# SN754410.net
KiCad netlist of a schematic drawn in EAGLE
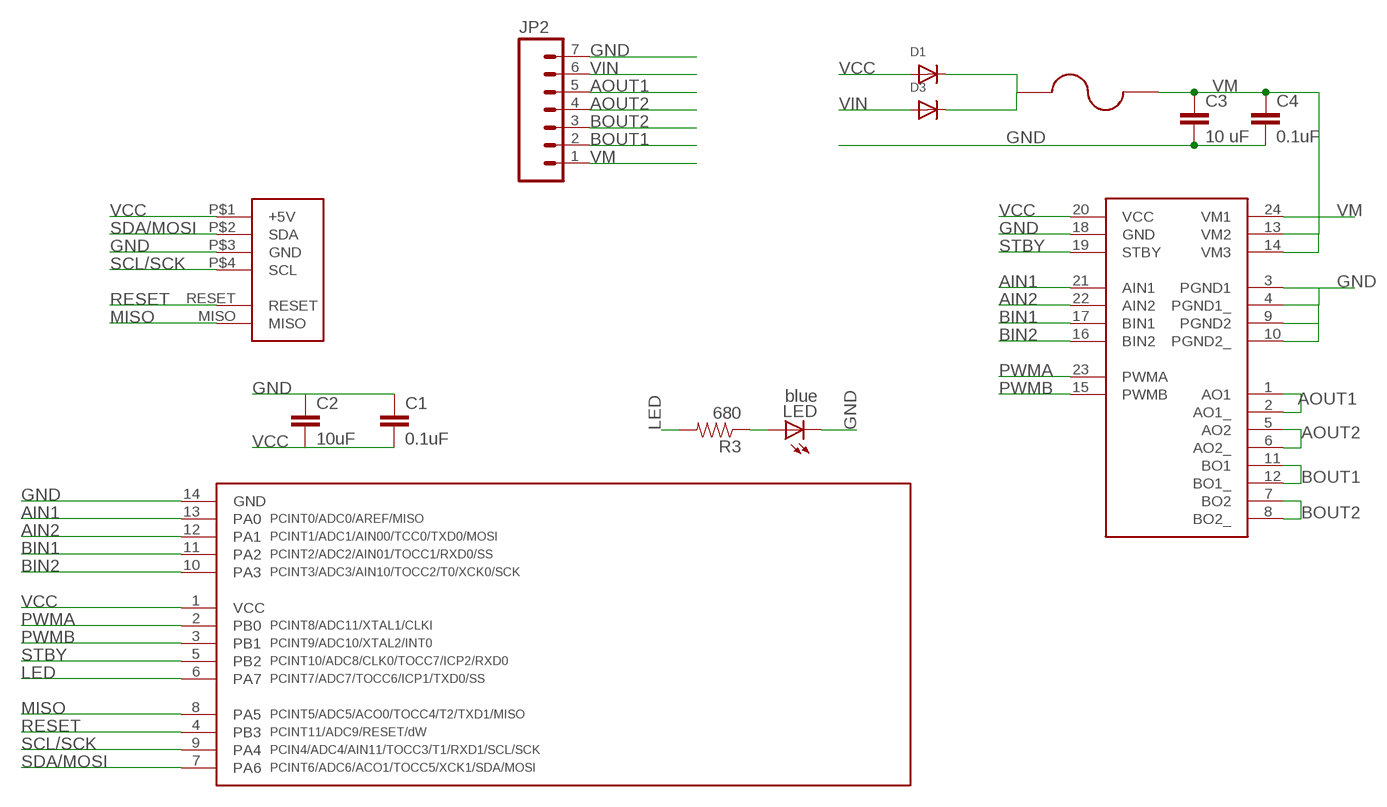
[diagram p0: schematic, sheet 1]

(export (version "E")
  (design (tool "Eeschema 10.0.6"))
  (components
    (comp (ref "C1")
      (value "0.1uF")
      (footprint "eagle-import:0805")
      (libsource (lib "eagle-import") (part "CAP0805"))
    )
    (comp (ref "C2")
      (value "10uF")
      (footprint "eagle-import:0805")
      (libsource (lib "eagle-import") (part "CAP0805"))
    )
    (comp (ref "C3")
      (value "10 uF")
      (footprint "eagle-import:0805")
      (libsource (lib "eagle-import") (part "CAP0805"))
    )
    (comp (ref "C4")
      (value "0.1uF")
      (footprint "eagle-import:0805")
      (libsource (lib "eagle-import") (part "CAP0805"))
    )
    (comp (ref "D1")
      (value "DIODESOD-123")
      (footprint "eagle-import:SOD-123")
      (libsource (lib "eagle-import") (part "DIODESOD-123"))
    )
    (comp (ref "D3")
      (value "DIODESOD-123")
      (footprint "eagle-import:SOD-123")
      (libsource (lib "eagle-import") (part "DIODESOD-123"))
    )
    (comp (ref "JP2")
      (value "M07")
      (footprint "eagle-import:1X07")
      (libsource (lib "eagle-import") (part "M07"))
    )
    (comp (ref "LED")
      (value "blue")
      (footprint "eagle-import:CHIPLED_1206")
      (libsource (lib "eagle-import") (part "LEDCHIPLED_1206"))
    )
    (comp (ref "R3")
      (value "680")
      (footprint "eagle-import:0805")
      (libsource (lib "eagle-import") (part "RESISTOR0805-RES"))
    )
    (comp (ref "U$1")
      (value "TB6612FNG")
      (footprint "eagle-import:SSOP-24")
      (libsource (lib "eagle-import") (part "TB6612FNG"))
    )
    (comp (ref "U$2")
      (value "FUSE")
      (footprint "eagle-import:1812")
      (libsource (lib "eagle-import") (part "FUSE"))
    )
    (comp (ref "U$3")
      (value "TINY841")
      (footprint "eagle-import:SOIC14")
      (libsource (lib "eagle-import") (part "TINY841"))
    )
    (comp (ref "U$4")
      (value "FOOTPRINT")
      (footprint "eagle-import:FOOTPRINT")
      (libsource (lib "eagle-import") (part "FOOTPRINT"))
    )
  )
  (nets
    (net (code "1") (name "/AIN1") (class "Default")
      (node (ref "U$1") (pin "21") (pinfunction "AIN1_21") (pintype "bidirectional"))
      (node (ref "U$3") (pin "13") (pinfunction "PA0_13") (pintype "bidirectional"))
    )
    (net (code "2") (name "/AIN2") (class "Default")
      (node (ref "U$1") (pin "22") (pinfunction "AIN2_22") (pintype "bidirectional"))
      (node (ref "U$3") (pin "12") (pinfunction "PA1_12") (pintype "bidirectional"))
    )
    (net (code "3") (name "/AOUT1") (class "Default")
      (node (ref "JP2") (pin "5") (pinfunction "5_5") (pintype "passive"))
      (node (ref "U$1") (pin "1") (pinfunction "AO1_1") (pintype "bidirectional"))
      (node (ref "U$1") (pin "2") (pinfunction "AO1__2") (pintype "bidirectional"))
    )
    (net (code "4") (name "/AOUT2") (class "Default")
      (node (ref "JP2") (pin "4") (pinfunction "4_4") (pintype "passive"))
      (node (ref "U$1") (pin "5") (pinfunction "AO2_5") (pintype "bidirectional"))
      (node (ref "U$1") (pin "6") (pinfunction "AO2__6") (pintype "bidirectional"))
    )
    (net (code "5") (name "/BIN1") (class "Default")
      (node (ref "U$1") (pin "17") (pinfunction "BIN1_17") (pintype "bidirectional"))
      (node (ref "U$3") (pin "11") (pinfunction "PA2_11") (pintype "bidirectional"))
    )
    (net (code "6") (name "/BIN2") (class "Default")
      (node (ref "U$1") (pin "16") (pinfunction "BIN2_16") (pintype "bidirectional"))
      (node (ref "U$3") (pin "10") (pinfunction "PA3_10") (pintype "bidirectional"))
    )
    (net (code "7") (name "/BOUT1") (class "Default")
      (node (ref "JP2") (pin "2") (pinfunction "2_2") (pintype "passive"))
      (node (ref "U$1") (pin "11") (pinfunction "BO1_11") (pintype "bidirectional"))
      (node (ref "U$1") (pin "12") (pinfunction "BO1__12") (pintype "bidirectional"))
    )
    (net (code "8") (name "/BOUT2") (class "Default")
      (node (ref "JP2") (pin "3") (pinfunction "3_3") (pintype "passive"))
      (node (ref "U$1") (pin "7") (pinfunction "BO2_7") (pintype "bidirectional"))
      (node (ref "U$1") (pin "8") (pinfunction "BO2__8") (pintype "bidirectional"))
    )
    (net (code "9") (name "/GND") (class "Default")
      (node (ref "C1") (pin "1") (pinfunction "1_1") (pintype "passive"))
      (node (ref "C2") (pin "1") (pinfunction "1_1") (pintype "passive"))
      (node (ref "C3") (pin "2") (pinfunction "2_2") (pintype "passive"))
      (node (ref "C4") (pin "2") (pinfunction "2_2") (pintype "passive"))
      (node (ref "JP2") (pin "7") (pinfunction "7_7") (pintype "passive"))
      (node (ref "LED") (pin "C") (pinfunction "C_C") (pintype "passive"))
      (node (ref "U$1") (pin "10") (pinfunction "PGND2__10") (pintype "bidirectional"))
      (node (ref "U$1") (pin "18") (pinfunction "GND_18") (pintype "bidirectional"))
      (node (ref "U$1") (pin "3") (pinfunction "PGND1_3") (pintype "bidirectional"))
      (node (ref "U$1") (pin "4") (pinfunction "PGND1__4") (pintype "bidirectional"))
      (node (ref "U$1") (pin "9") (pinfunction "PGND2_9") (pintype "bidirectional"))
      (node (ref "U$3") (pin "14") (pinfunction "GND_14") (pintype "bidirectional"))
      (node (ref "U$4") (pin "P$3") (pinfunction "GND_P$3") (pintype "power_in"))
    )
    (net (code "10") (name "/LED") (class "Default")
      (node (ref "R3") (pin "2") (pinfunction "2_2") (pintype "passive"))
      (node (ref "U$3") (pin "6") (pinfunction "PA7_6") (pintype "bidirectional"))
    )
    (net (code "11") (name "/MISO") (class "Default")
      (node (ref "U$3") (pin "8") (pinfunction "PA5_8") (pintype "bidirectional"))
      (node (ref "U$4") (pin "MISO") (pinfunction "MISO_MISO") (pintype "bidirectional"))
    )
    (net (code "12") (name "/PWMA") (class "Default")
      (node (ref "U$1") (pin "23") (pinfunction "PWMA_23") (pintype "bidirectional"))
      (node (ref "U$3") (pin "2") (pinfunction "PB0_2") (pintype "bidirectional"))
    )
    (net (code "13") (name "/PWMB") (class "Default")
      (node (ref "U$1") (pin "15") (pinfunction "PWMB_15") (pintype "bidirectional"))
      (node (ref "U$3") (pin "3") (pinfunction "PB1_3") (pintype "bidirectional"))
    )
    (net (code "14") (name "/RESET") (class "Default")
      (node (ref "U$3") (pin "4") (pinfunction "PB3_4") (pintype "bidirectional"))
      (node (ref "U$4") (pin "RESET") (pinfunction "RESET_RESET") (pintype "bidirectional"))
    )
    (net (code "15") (name "/SCL{slash}SCK") (class "Default")
      (node (ref "U$3") (pin "9") (pinfunction "PA4_9") (pintype "bidirectional"))
      (node (ref "U$4") (pin "P$4") (pinfunction "SCL_P$4") (pintype "bidirectional"))
    )
    (net (code "16") (name "/SDA{slash}MOSI") (class "Default")
      (node (ref "U$3") (pin "7") (pinfunction "PA6_7") (pintype "bidirectional"))
      (node (ref "U$4") (pin "P$2") (pinfunction "SDA_P$2") (pintype "bidirectional"))
    )
    (net (code "17") (name "/STBY") (class "Default")
      (node (ref "U$1") (pin "19") (pinfunction "STBY_19") (pintype "bidirectional"))
      (node (ref "U$3") (pin "5") (pinfunction "PB2_5") (pintype "bidirectional"))
    )
    (net (code "18") (name "/VCC") (class "Default")
      (node (ref "C1") (pin "2") (pinfunction "2_2") (pintype "passive"))
      (node (ref "C2") (pin "2") (pinfunction "2_2") (pintype "passive"))
      (node (ref "D1") (pin "A") (pinfunction "A_A") (pintype "passive"))
      (node (ref "U$1") (pin "20") (pinfunction "VCC_20") (pintype "bidirectional"))
      (node (ref "U$3") (pin "1") (pinfunction "VCC_1") (pintype "bidirectional"))
      (node (ref "U$4") (pin "P$1") (pinfunction "+5V_P$1") (pintype "power_in"))
    )
    (net (code "19") (name "/VIN") (class "Default")
      (node (ref "D3") (pin "A") (pinfunction "A_A") (pintype "passive"))
      (node (ref "JP2") (pin "6") (pinfunction "6_6") (pintype "passive"))
    )
    (net (code "20") (name "/VM") (class "Default")
      (node (ref "C3") (pin "1") (pinfunction "1_1") (pintype "passive"))
      (node (ref "C4") (pin "1") (pinfunction "1_1") (pintype "passive"))
      (node (ref "JP2") (pin "1") (pinfunction "1_1") (pintype "passive"))
      (node (ref "U$1") (pin "13") (pinfunction "VM2_13") (pintype "bidirectional"))
      (node (ref "U$1") (pin "14") (pinfunction "VM3_14") (pintype "bidirectional"))
      (node (ref "U$1") (pin "24") (pinfunction "VM1_24") (pintype "bidirectional"))
      (node (ref "U$2") (pin "P$2") (pinfunction "2_P$2") (pintype "bidirectional"))
    )
    (net (code "21") (name "Net-(LED-PadA)") (class "Default")
      (node (ref "LED") (pin "A") (pinfunction "A_A") (pintype "passive"))
      (node (ref "R3") (pin "1") (pinfunction "1_1") (pintype "passive"))
    )
    (net (code "22") (name "Net-(U$2-1)") (class "Default")
      (node (ref "D1") (pin "C") (pinfunction "C_C") (pintype "passive"))
      (node (ref "D3") (pin "C") (pinfunction "C_C") (pintype "passive"))
      (node (ref "U$2") (pin "P$1") (pinfunction "1_P$1") (pintype "bidirectional"))
    )
  )
)
